# ct_fpga_pwr.net
KiCad netlist of a schematic drawn in Altium Designer
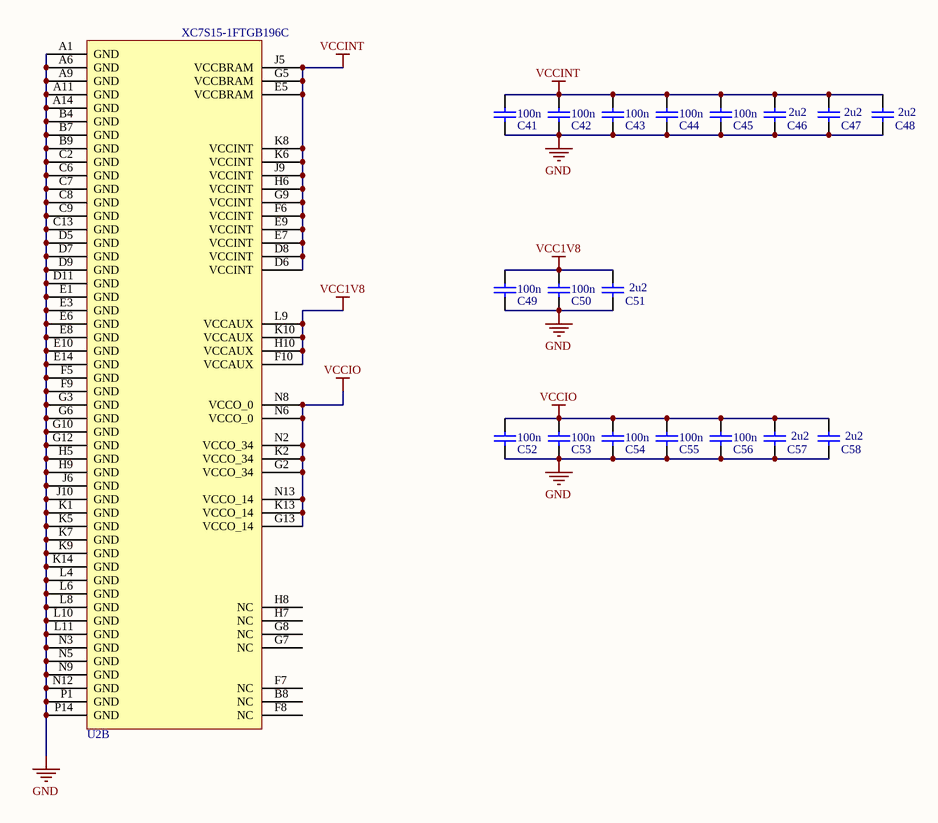
[diagram p0: ct_fpga_pwr.SchDoc]

(export (version "E")
  (design (tool "Eeschema 10.0.6"))
  (components
    (comp (ref "C41")
      (value "100n")
      (footprint "CAPC0402_M")
      (description "100n, 0402")
      (fields (field (name "PART NUMBER") "CCHIP-100n-0402"))
      (libsource (lib "NewAE_AltiumLib") (part "CAP"))
    )
    (comp (ref "C42")
      (value "100n")
      (footprint "CAPC0402_M")
      (description "100n, 0402")
      (fields (field (name "PART NUMBER") "CCHIP-100n-0402"))
      (libsource (lib "NewAE_AltiumLib") (part "CAP"))
    )
    (comp (ref "C43")
      (value "100n")
      (footprint "CAPC0402_M")
      (description "100n, 0402")
      (fields (field (name "PART NUMBER") "CCHIP-100n-0402"))
      (libsource (lib "NewAE_AltiumLib") (part "CAP"))
    )
    (comp (ref "C44")
      (value "100n")
      (footprint "CAPC0402_M")
      (description "100n, 0402")
      (fields (field (name "PART NUMBER") "CCHIP-100n-0402"))
      (libsource (lib "NewAE_AltiumLib") (part "CAP"))
    )
    (comp (ref "C45")
      (value "100n")
      (footprint "CAPC0402_M")
      (description "100n, 0402")
      (fields (field (name "PART NUMBER") "CCHIP-100n-0402"))
      (libsource (lib "NewAE_AltiumLib") (part "CAP"))
    )
    (comp (ref "C46")
      (value "2u2")
      (footprint "CAPC0603_M")
      (description "2u2, 0603")
      (fields (field (name "PART NUMBER") "CCHIP-2u2-0603"))
      (libsource (lib "NewAE_AltiumLib") (part "CAP"))
    )
    (comp (ref "C47")
      (value "2u2")
      (footprint "CAPC0603_M")
      (description "2u2, 0603")
      (fields (field (name "PART NUMBER") "CCHIP-2u2-0603"))
      (libsource (lib "NewAE_AltiumLib") (part "CAP"))
    )
    (comp (ref "C48")
      (value "2u2")
      (footprint "CAPC0603_M")
      (description "2u2, 0603")
      (fields (field (name "PART NUMBER") "CCHIP-2u2-0603"))
      (libsource (lib "NewAE_AltiumLib") (part "CAP"))
    )
    (comp (ref "C49")
      (value "100n")
      (footprint "CAPC0402_M")
      (description "100n, 0402")
      (fields (field (name "PART NUMBER") "CCHIP-100n-0402"))
      (libsource (lib "NewAE_AltiumLib") (part "CAP"))
    )
    (comp (ref "C50")
      (value "100n")
      (footprint "CAPC0402_M")
      (description "100n, 0402")
      (fields (field (name "PART NUMBER") "CCHIP-100n-0402"))
      (libsource (lib "NewAE_AltiumLib") (part "CAP"))
    )
    (comp (ref "C51")
      (value "2u2")
      (footprint "CAPC0603_M")
      (description "2u2, 0603")
      (fields (field (name "PART NUMBER") "CCHIP-2u2-0603"))
      (libsource (lib "NewAE_AltiumLib") (part "CAP"))
    )
    (comp (ref "C52")
      (value "100n")
      (footprint "CAPC0402_M")
      (description "100n, 0402")
      (fields (field (name "PART NUMBER") "CCHIP-100n-0402"))
      (libsource (lib "NewAE_AltiumLib") (part "CAP"))
    )
    (comp (ref "C53")
      (value "100n")
      (footprint "CAPC0402_M")
      (description "100n, 0402")
      (fields (field (name "PART NUMBER") "CCHIP-100n-0402"))
      (libsource (lib "NewAE_AltiumLib") (part "CAP"))
    )
    (comp (ref "C54")
      (value "100n")
      (footprint "CAPC0402_M")
      (description "100n, 0402")
      (fields (field (name "PART NUMBER") "CCHIP-100n-0402"))
      (libsource (lib "NewAE_AltiumLib") (part "CAP"))
    )
    (comp (ref "C55")
      (value "100n")
      (footprint "CAPC0402_M")
      (description "100n, 0402")
      (fields (field (name "PART NUMBER") "CCHIP-100n-0402"))
      (libsource (lib "NewAE_AltiumLib") (part "CAP"))
    )
    (comp (ref "C56")
      (value "100n")
      (footprint "CAPC0402_M")
      (description "100n, 0402")
      (fields (field (name "PART NUMBER") "CCHIP-100n-0402"))
      (libsource (lib "NewAE_AltiumLib") (part "CAP"))
    )
    (comp (ref "C57")
      (value "2u2")
      (footprint "CAPC0603_M")
      (description "2u2, 0603")
      (fields (field (name "PART NUMBER") "CCHIP-2u2-0603"))
      (libsource (lib "NewAE_AltiumLib") (part "CAP"))
    )
    (comp (ref "C58")
      (value "2u2")
      (footprint "CAPC0603_M")
      (description "2u2, 0603")
      (fields (field (name "PART NUMBER") "CCHIP-2u2-0603"))
      (libsource (lib "NewAE_AltiumLib") (part "CAP"))
    )
    (comp (ref "U2")
      (value "XC7S15-1FTGB196C")
      (footprint "BGA_FTGB196")
      (description "Xilinx Spartan 7 FPGA, 196FTGB")
      (libsource (lib "NewAE_AltiumLib") (part "XC7S6FTGB196"))
    )
  )
  (nets
    (net (code "1") (name "GND") (class "Default")
      (node (ref "C41") (pin "2") (pinfunction "2_2") (pintype "passive"))
      (node (ref "C42") (pin "2") (pinfunction "2_2") (pintype "passive"))
      (node (ref "C43") (pin "2") (pinfunction "2_2") (pintype "passive"))
      (node (ref "C44") (pin "2") (pinfunction "2_2") (pintype "passive"))
      (node (ref "C45") (pin "2") (pinfunction "2_2") (pintype "passive"))
      (node (ref "C46") (pin "2") (pinfunction "2_2") (pintype "passive"))
      (node (ref "C47") (pin "2") (pinfunction "2_2") (pintype "passive"))
      (node (ref "C48") (pin "2") (pinfunction "2_2") (pintype "passive"))
      (node (ref "C49") (pin "2") (pinfunction "2_2") (pintype "passive"))
      (node (ref "C50") (pin "2") (pinfunction "2_2") (pintype "passive"))
      (node (ref "C51") (pin "2") (pinfunction "2_2") (pintype "passive"))
      (node (ref "C52") (pin "2") (pinfunction "2_2") (pintype "passive"))
      (node (ref "C53") (pin "2") (pinfunction "2_2") (pintype "passive"))
      (node (ref "C54") (pin "2") (pinfunction "2_2") (pintype "passive"))
      (node (ref "C55") (pin "2") (pinfunction "2_2") (pintype "passive"))
      (node (ref "C56") (pin "2") (pinfunction "2_2") (pintype "passive"))
      (node (ref "C57") (pin "2") (pinfunction "2_2") (pintype "passive"))
      (node (ref "C58") (pin "2") (pinfunction "2_2") (pintype "passive"))
      (node (ref "U2") (pin "A1") (pinfunction "GND_A1") (pintype "power_in"))
      (node (ref "U2") (pin "A11") (pinfunction "GND_A11") (pintype "power_in"))
      (node (ref "U2") (pin "A14") (pinfunction "GND_A14") (pintype "power_in"))
      (node (ref "U2") (pin "A6") (pinfunction "GND_A6") (pintype "power_in"))
      (node (ref "U2") (pin "A9") (pinfunction "GND_A9") (pintype "power_in"))
      (node (ref "U2") (pin "B4") (pinfunction "GND_B4") (pintype "power_in"))
      (node (ref "U2") (pin "B7") (pinfunction "GND_B7") (pintype "power_in"))
      (node (ref "U2") (pin "B9") (pinfunction "GND_B9") (pintype "power_in"))
      (node (ref "U2") (pin "C13") (pinfunction "GND_C13") (pintype "power_in"))
      (node (ref "U2") (pin "C2") (pinfunction "GND_C2") (pintype "power_in"))
      (node (ref "U2") (pin "C6") (pinfunction "GND_C6") (pintype "power_in"))
      (node (ref "U2") (pin "C7") (pinfunction "GND_C7") (pintype "power_in"))
      (node (ref "U2") (pin "C8") (pinfunction "GND_C8") (pintype "power_in"))
      (node (ref "U2") (pin "C9") (pinfunction "GND_C9") (pintype "power_in"))
      (node (ref "U2") (pin "D11") (pinfunction "GND_D11") (pintype "power_in"))
      (node (ref "U2") (pin "D5") (pinfunction "GND_D5") (pintype "power_in"))
      (node (ref "U2") (pin "D7") (pinfunction "GND_D7") (pintype "power_in"))
      (node (ref "U2") (pin "D9") (pinfunction "GND_D9") (pintype "power_in"))
      (node (ref "U2") (pin "E1") (pinfunction "GND_E1") (pintype "power_in"))
      (node (ref "U2") (pin "E10") (pinfunction "GND_E10") (pintype "power_in"))
      (node (ref "U2") (pin "E14") (pinfunction "GND_E14") (pintype "power_in"))
      (node (ref "U2") (pin "E3") (pinfunction "GND_E3") (pintype "power_in"))
      (node (ref "U2") (pin "E6") (pinfunction "GND_E6") (pintype "power_in"))
      (node (ref "U2") (pin "E8") (pinfunction "GND_E8") (pintype "power_in"))
      (node (ref "U2") (pin "F5") (pinfunction "GND_F5") (pintype "power_in"))
      (node (ref "U2") (pin "F9") (pinfunction "GND_F9") (pintype "power_in"))
      (node (ref "U2") (pin "G10") (pinfunction "GND_G10") (pintype "power_in"))
      (node (ref "U2") (pin "G12") (pinfunction "GND_G12") (pintype "power_in"))
      (node (ref "U2") (pin "G3") (pinfunction "GND_G3") (pintype "power_in"))
      (node (ref "U2") (pin "G6") (pinfunction "GND_G6") (pintype "power_in"))
      (node (ref "U2") (pin "H5") (pinfunction "GND_H5") (pintype "power_in"))
      (node (ref "U2") (pin "H9") (pinfunction "GND_H9") (pintype "power_in"))
      (node (ref "U2") (pin "J10") (pinfunction "GND_J10") (pintype "power_in"))
      (node (ref "U2") (pin "J6") (pinfunction "GND_J6") (pintype "power_in"))
      (node (ref "U2") (pin "K1") (pinfunction "GND_K1") (pintype "power_in"))
      (node (ref "U2") (pin "K14") (pinfunction "GND_K14") (pintype "power_in"))
      (node (ref "U2") (pin "K5") (pinfunction "GND_K5") (pintype "power_in"))
      (node (ref "U2") (pin "K7") (pinfunction "GND_K7") (pintype "power_in"))
      (node (ref "U2") (pin "K9") (pinfunction "GND_K9") (pintype "power_in"))
      (node (ref "U2") (pin "L10") (pinfunction "GND_L10") (pintype "power_in"))
      (node (ref "U2") (pin "L11") (pinfunction "GND_L11") (pintype "power_in"))
      (node (ref "U2") (pin "L4") (pinfunction "GND_L4") (pintype "power_in"))
      (node (ref "U2") (pin "L6") (pinfunction "GND_L6") (pintype "power_in"))
      (node (ref "U2") (pin "L8") (pinfunction "GND_L8") (pintype "power_in"))
      (node (ref "U2") (pin "N12") (pinfunction "GND_N12") (pintype "power_in"))
      (node (ref "U2") (pin "N3") (pinfunction "GND_N3") (pintype "power_in"))
      (node (ref "U2") (pin "N5") (pinfunction "GND_N5") (pintype "power_in"))
      (node (ref "U2") (pin "N9") (pinfunction "GND_N9") (pintype "power_in"))
      (node (ref "U2") (pin "P1") (pinfunction "GND_P1") (pintype "power_in"))
      (node (ref "U2") (pin "P14") (pinfunction "GND_P14") (pintype "power_in"))
    )
    (net (code "2") (name "VCC1V8") (class "Default")
      (node (ref "C49") (pin "1") (pinfunction "1_1") (pintype "passive"))
      (node (ref "C50") (pin "1") (pinfunction "1_1") (pintype "passive"))
      (node (ref "C51") (pin "1") (pinfunction "1_1") (pintype "passive"))
      (node (ref "U2") (pin "F10") (pinfunction "VCCAUX_F10") (pintype "power_in"))
      (node (ref "U2") (pin "H10") (pinfunction "VCCAUX_H10") (pintype "power_in"))
      (node (ref "U2") (pin "K10") (pinfunction "VCCAUX_K10") (pintype "power_in"))
      (node (ref "U2") (pin "L9") (pinfunction "VCCAUX_L9") (pintype "power_in"))
    )
    (net (code "3") (name "VCCINT") (class "Default")
      (node (ref "C41") (pin "1") (pinfunction "1_1") (pintype "passive"))
      (node (ref "C42") (pin "1") (pinfunction "1_1") (pintype "passive"))
      (node (ref "C43") (pin "1") (pinfunction "1_1") (pintype "passive"))
      (node (ref "C44") (pin "1") (pinfunction "1_1") (pintype "passive"))
      (node (ref "C45") (pin "1") (pinfunction "1_1") (pintype "passive"))
      (node (ref "C46") (pin "1") (pinfunction "1_1") (pintype "passive"))
      (node (ref "C47") (pin "1") (pinfunction "1_1") (pintype "passive"))
      (node (ref "C48") (pin "1") (pinfunction "1_1") (pintype "passive"))
      (node (ref "U2") (pin "D6") (pinfunction "VCCINT_D6") (pintype "power_in"))
      (node (ref "U2") (pin "D8") (pinfunction "VCCINT_D8") (pintype "power_in"))
      (node (ref "U2") (pin "E5") (pinfunction "VCCBRAM_E5") (pintype "power_in"))
      (node (ref "U2") (pin "E7") (pinfunction "VCCINT_E7") (pintype "power_in"))
      (node (ref "U2") (pin "E9") (pinfunction "VCCINT_E9") (pintype "power_in"))
      (node (ref "U2") (pin "F6") (pinfunction "VCCINT_F6") (pintype "power_in"))
      (node (ref "U2") (pin "G5") (pinfunction "VCCBRAM_G5") (pintype "power_in"))
      (node (ref "U2") (pin "G9") (pinfunction "VCCINT_G9") (pintype "power_in"))
      (node (ref "U2") (pin "H6") (pinfunction "VCCINT_H6") (pintype "power_in"))
      (node (ref "U2") (pin "J5") (pinfunction "VCCBRAM_J5") (pintype "power_in"))
      (node (ref "U2") (pin "J9") (pinfunction "VCCINT_J9") (pintype "power_in"))
      (node (ref "U2") (pin "K6") (pinfunction "VCCINT_K6") (pintype "power_in"))
      (node (ref "U2") (pin "K8") (pinfunction "VCCINT_K8") (pintype "power_in"))
    )
    (net (code "4") (name "VCCIO") (class "Default")
      (node (ref "C52") (pin "1") (pinfunction "1_1") (pintype "passive"))
      (node (ref "C53") (pin "1") (pinfunction "1_1") (pintype "passive"))
      (node (ref "C54") (pin "1") (pinfunction "1_1") (pintype "passive"))
      (node (ref "C55") (pin "1") (pinfunction "1_1") (pintype "passive"))
      (node (ref "C56") (pin "1") (pinfunction "1_1") (pintype "passive"))
      (node (ref "C57") (pin "1") (pinfunction "1_1") (pintype "passive"))
      (node (ref "C58") (pin "1") (pinfunction "1_1") (pintype "passive"))
      (node (ref "U2") (pin "G13") (pinfunction "VCCO_14_G13") (pintype "power_in"))
      (node (ref "U2") (pin "G2") (pinfunction "VCCO_34_G2") (pintype "power_in"))
      (node (ref "U2") (pin "K13") (pinfunction "VCCO_14_K13") (pintype "power_in"))
      (node (ref "U2") (pin "K2") (pinfunction "VCCO_34_K2") (pintype "power_in"))
      (node (ref "U2") (pin "N13") (pinfunction "VCCO_14_N13") (pintype "power_in"))
      (node (ref "U2") (pin "N2") (pinfunction "VCCO_34_N2") (pintype "power_in"))
      (node (ref "U2") (pin "N6") (pinfunction "VCCO_0_N6") (pintype "power_in"))
      (node (ref "U2") (pin "N8") (pinfunction "VCCO_0_N8") (pintype "power_in"))
    )
    (net (code "5") (name "unconnected-(U2B-NC-PadB8)") (class "Default")
      (node (ref "U2") (pin "B8") (pinfunction "NC_B8") (pintype "passive"))
    )
    (net (code "6") (name "unconnected-(U2B-NC-PadF7)") (class "Default")
      (node (ref "U2") (pin "F7") (pinfunction "NC_F7") (pintype "passive"))
    )
    (net (code "7") (name "unconnected-(U2B-NC-PadF8)") (class "Default")
      (node (ref "U2") (pin "F8") (pinfunction "NC_F8") (pintype "passive"))
    )
    (net (code "8") (name "unconnected-(U2B-NC-PadG7)") (class "Default")
      (node (ref "U2") (pin "G7") (pinfunction "NC_G7") (pintype "passive"))
    )
    (net (code "9") (name "unconnected-(U2B-NC-PadG8)") (class "Default")
      (node (ref "U2") (pin "G8") (pinfunction "NC_G8") (pintype "passive"))
    )
    (net (code "10") (name "unconnected-(U2B-NC-PadH7)") (class "Default")
      (node (ref "U2") (pin "H7") (pinfunction "NC_H7") (pintype "passive"))
    )
    (net (code "11") (name "unconnected-(U2B-NC-PadH8)") (class "Default")
      (node (ref "U2") (pin "H8") (pinfunction "NC_H8") (pintype "passive"))
    )
  )
)
